# design.net
KiCad netlist of a schematic drawn in EasyEDA
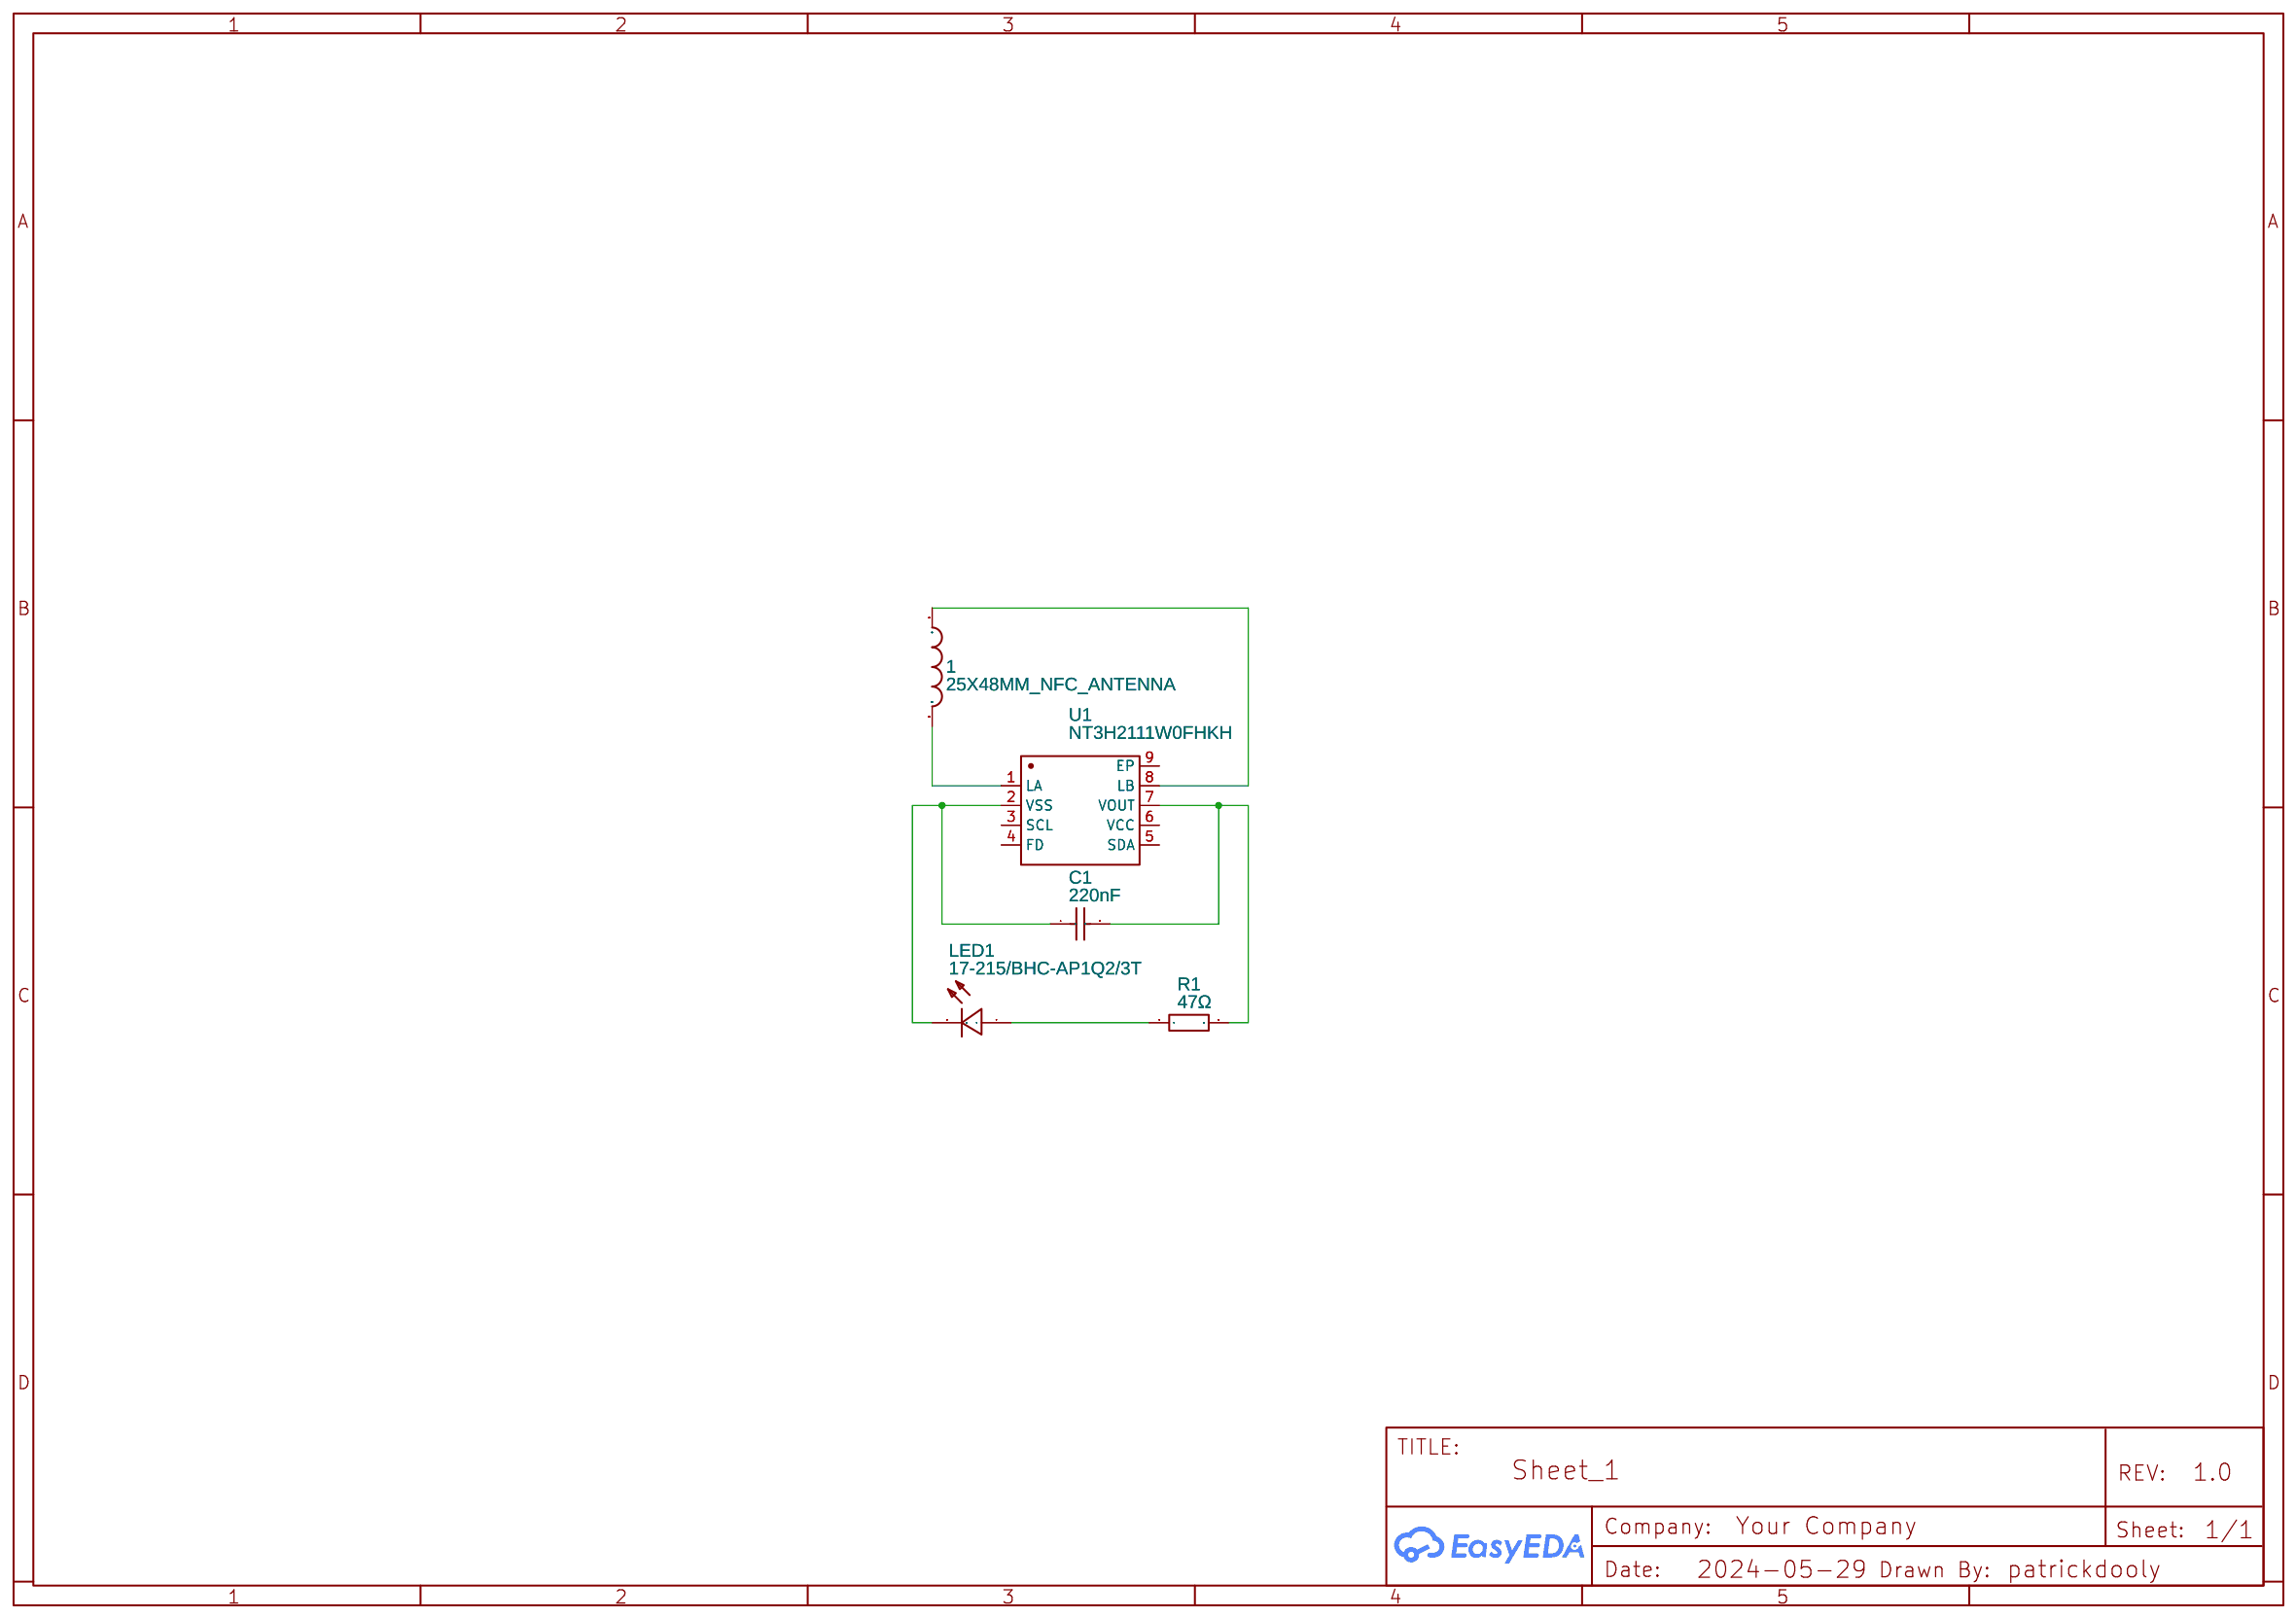
[diagram p0: schematic sheet]

(export (version "E")
  (design (tool "Eeschema 10.0.6"))
  (components
    (comp (ref "1") (value "25X48MM_NFC_ANTENNA") (libsource (lib "") (part "25X48MM_NFC_ANTENNA")))
    (comp (ref "C1")
      (value "220nF")
      (fields
        (field (name "Manufacturer Part") "CL10B224KA8NNNC")
        (field (name "Manufacturer") "SAMSUNG(三星)")
      )
      (libsource (lib "") (part "CL10B224KA8NNNC"))
    )
    (comp (ref "LED1")
      (value "17-215/BHC-AP1Q2/3T")
      (fields (field (name "Manufacturer") "EVERLIGHT(亿光)"))
      (libsource (lib "") (part "17-215/BHC-AP1Q2/3T"))
    )
    (comp (ref "R1")
      (value "47Ω")
      (fields
        (field (name "Manufacturer Part") "0603WAF470JT5E")
        (field (name "Manufacturer") "UNI-ROYAL(厚声)")
      )
      (libsource (lib "") (part "0603WAF470JT5E"))
    )
    (comp (ref "U1")
      (value "NT3H2111W0FHKH")
      (fields (field (name "Manufacturer") "NXP(恩智浦)"))
      (libsource (lib "") (part "NT3H2111W0FHKH"))
    )
  )
  (nets
    (net (code "1") (name "Net-(LED1-Pad1)") (class "Default")
      (node (ref "LED1") (pin "1") (pinfunction "1_1") (pintype "unspecified"))
      (node (ref "R1") (pin "1") (pinfunction "1_1") (pintype "input"))
    )
    (net (code "2") (name "Net-(U1-LA)") (class "Default")
      (node (ref "1") (pin "P$2") (pinfunction "P$2_P$2") (pintype "bidirectional"))
      (node (ref "U1") (pin "1") (pinfunction "LA_1") (pintype "unspecified"))
    )
    (net (code "3") (name "Net-(U1-LB)") (class "Default")
      (node (ref "1") (pin "P$1") (pinfunction "P$1_P$1") (pintype "bidirectional"))
      (node (ref "U1") (pin "8") (pinfunction "LB_8") (pintype "unspecified"))
    )
    (net (code "4") (name "Net-(U1-VOUT)") (class "Default")
      (node (ref "C1") (pin "2") (pinfunction "2_2") (pintype "input"))
      (node (ref "R1") (pin "2") (pinfunction "2_2") (pintype "input"))
      (node (ref "U1") (pin "7") (pinfunction "VOUT_7") (pintype "unspecified"))
    )
    (net (code "5") (name "Net-(U1-VSS)") (class "Default")
      (node (ref "C1") (pin "1") (pinfunction "1_1") (pintype "input"))
      (node (ref "LED1") (pin "2") (pinfunction "2_2") (pintype "unspecified"))
      (node (ref "U1") (pin "2") (pinfunction "VSS_2") (pintype "unspecified"))
    )
    (net (code "6") (name "unconnected-(U1-EP-Pad9)") (class "Default")
      (node (ref "U1") (pin "9") (pinfunction "EP_9") (pintype "unspecified"))
    )
    (net (code "7") (name "unconnected-(U1-FD-Pad4)") (class "Default")
      (node (ref "U1") (pin "4") (pinfunction "FD_4") (pintype "unspecified"))
    )
    (net (code "8") (name "unconnected-(U1-SCL-Pad3)") (class "Default")
      (node (ref "U1") (pin "3") (pinfunction "SCL_3") (pintype "unspecified"))
    )
    (net (code "9") (name "unconnected-(U1-SDA-Pad5)") (class "Default")
      (node (ref "U1") (pin "5") (pinfunction "SDA_5") (pintype "unspecified"))
    )
    (net (code "10") (name "unconnected-(U1-VCC-Pad6)") (class "Default")
      (node (ref "U1") (pin "6") (pinfunction "VCC_6") (pintype "unspecified"))
    )
  )
)
